# DuplexOptoIso.net
KiCad netlist of a schematic drawn in EAGLE
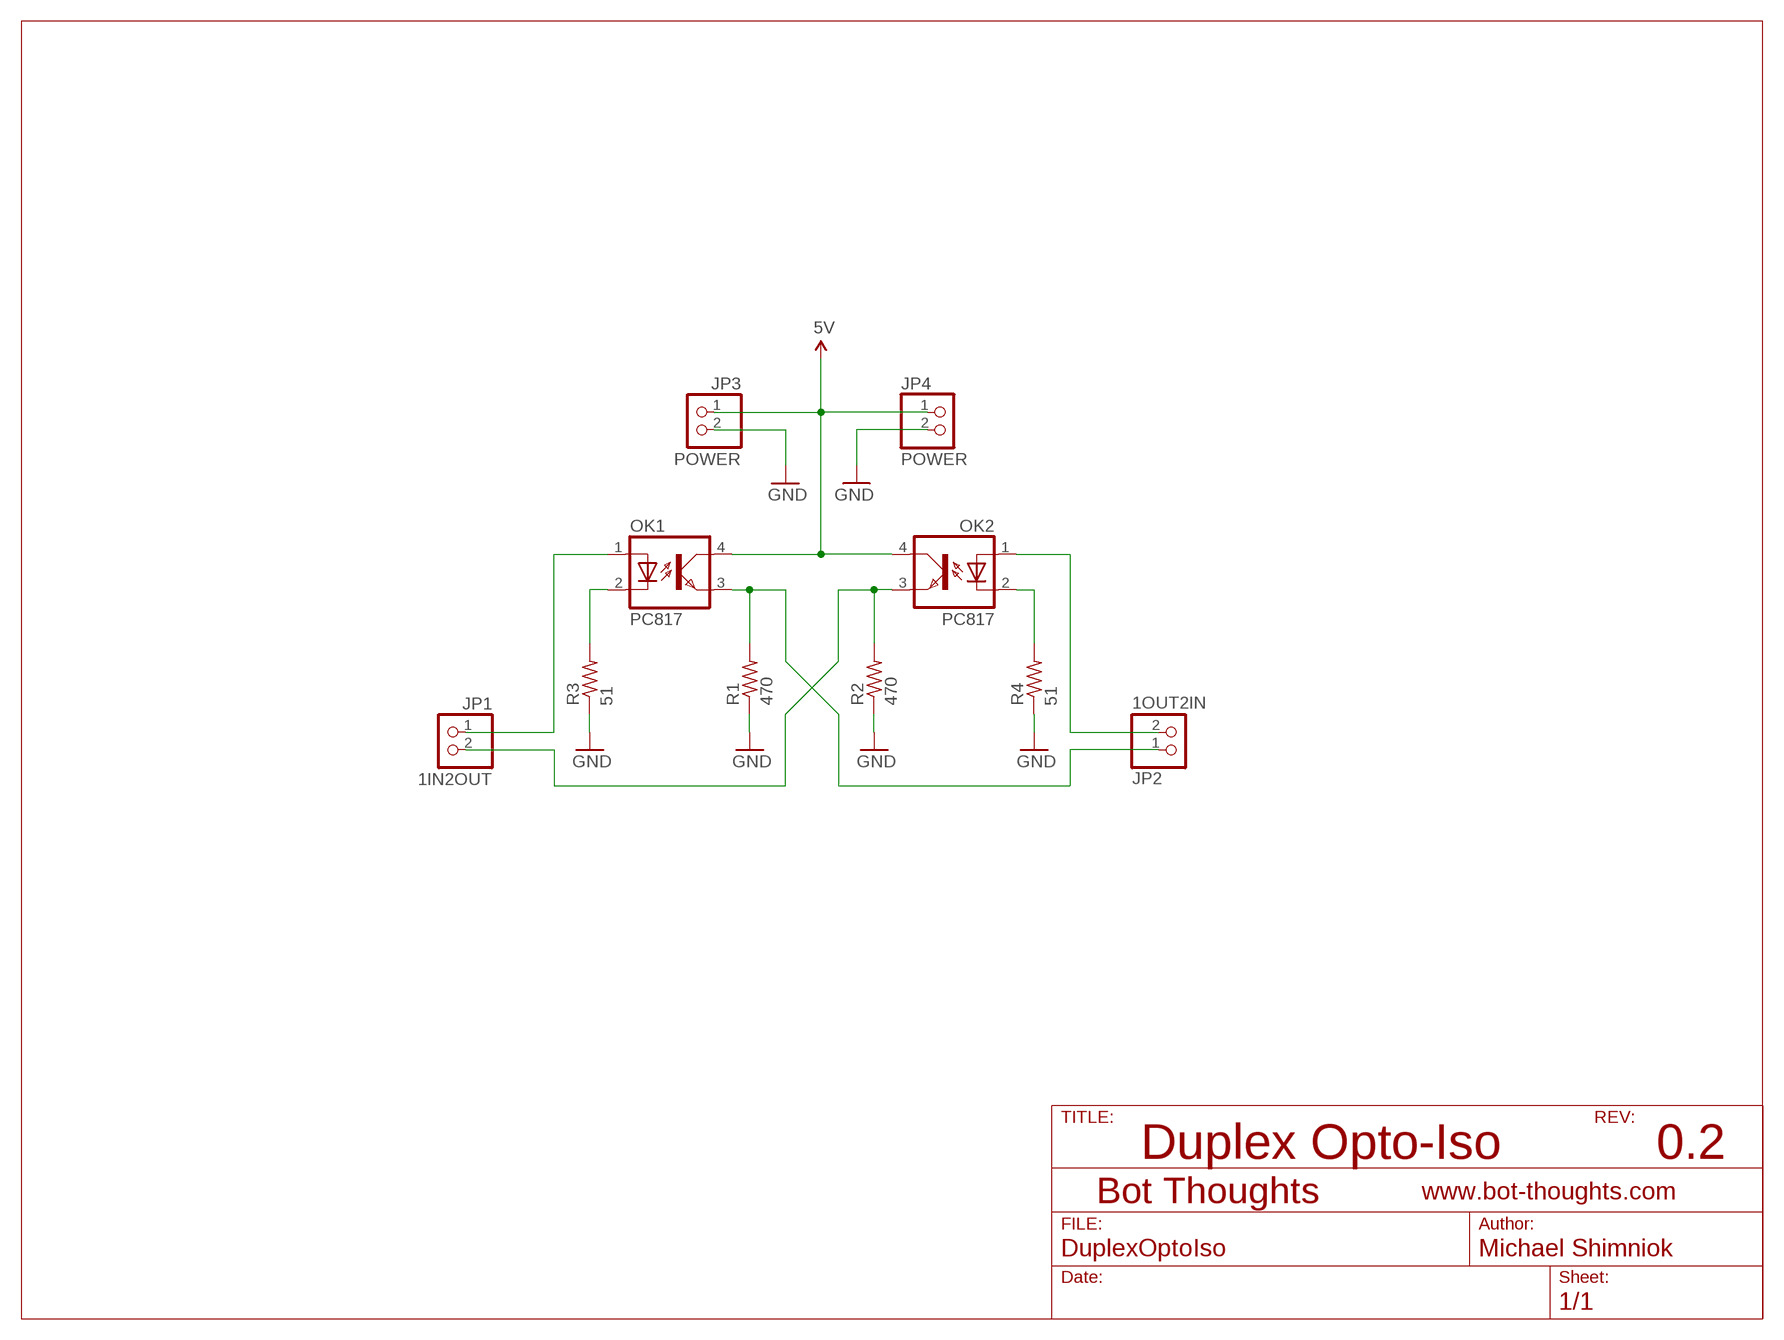
[diagram p0: schematic, sheet 1]

(export (version "E")
  (design (tool "Eeschema 10.0.6"))
  (components
    (comp (ref "JP1")
      (value "1IN2OUT")
      (footprint "eagle-import:1X02-S")
      (libsource (lib "eagle-import") (part "PINHD-1X02_2.54-S"))
    )
    (comp (ref "JP2")
      (value "1OUT2IN")
      (footprint "eagle-import:1X02-S")
      (libsource (lib "eagle-import") (part "PINHD-1X02_2.54-S"))
    )
    (comp (ref "JP3")
      (value "POWER")
      (footprint "eagle-import:1X02-S")
      (libsource (lib "eagle-import") (part "PINHD-1X02_2.54-S"))
    )
    (comp (ref "JP4")
      (value "POWER")
      (footprint "eagle-import:1X02-S")
      (libsource (lib "eagle-import") (part "PINHD-1X02_2.54-S"))
    )
    (comp (ref "OK1")
      (value "PC817")
      (footprint "eagle-import:DIL04")
      (fields (field (name "MPN") "PC817X4J000F"))
      (libsource (lib "eagle-import") (part "PC817"))
    )
    (comp (ref "OK2")
      (value "PC817")
      (footprint "eagle-import:DIL04")
      (fields (field (name "MPN") "PC817X4J000F"))
      (libsource (lib "eagle-import") (part "PC817"))
    )
    (comp (ref "R1")
      (value "470")
      (footprint "eagle-import:0204_5")
      (libsource (lib "eagle-import") (part "R-US_0204/5"))
    )
    (comp (ref "R2")
      (value "470")
      (footprint "eagle-import:0204_5")
      (libsource (lib "eagle-import") (part "R-US_0204/5"))
    )
    (comp (ref "R3")
      (value "51")
      (footprint "eagle-import:0204_5")
      (libsource (lib "eagle-import") (part "R-US_0204/5"))
    )
    (comp (ref "R4")
      (value "51")
      (footprint "eagle-import:0204_5")
      (libsource (lib "eagle-import") (part "R-US_0204/5"))
    )
  )
  (nets
    (net (code "1") (name "5V") (class "Default")
      (node (ref "JP3") (pin "1") (pinfunction "1_1") (pintype "passive"))
      (node (ref "JP4") (pin "1") (pinfunction "1_1") (pintype "passive"))
      (node (ref "OK1") (pin "4") (pinfunction "COL_4") (pintype "passive"))
      (node (ref "OK2") (pin "4") (pinfunction "COL_4") (pintype "passive"))
    )
    (net (code "2") (name "GND") (class "Default")
      (node (ref "JP3") (pin "2") (pinfunction "2_2") (pintype "passive"))
      (node (ref "JP4") (pin "2") (pinfunction "2_2") (pintype "passive"))
      (node (ref "R1") (pin "1") (pinfunction "1_1") (pintype "passive"))
      (node (ref "R2") (pin "1") (pinfunction "1_1") (pintype "passive"))
      (node (ref "R3") (pin "1") (pinfunction "1_1") (pintype "passive"))
      (node (ref "R4") (pin "1") (pinfunction "1_1") (pintype "passive"))
    )
    (net (code "3") (name "Net-(OK1-A)") (class "Default")
      (node (ref "JP1") (pin "1") (pinfunction "1_1") (pintype "passive"))
      (node (ref "OK1") (pin "1") (pinfunction "A_1") (pintype "passive"))
    )
    (net (code "4") (name "Net-(OK1-C)") (class "Default")
      (node (ref "OK1") (pin "2") (pinfunction "C_2") (pintype "passive"))
      (node (ref "R3") (pin "2") (pinfunction "2_2") (pintype "passive"))
    )
    (net (code "5") (name "Net-(OK1-EMIT)") (class "Default")
      (node (ref "JP2") (pin "1") (pinfunction "1_1") (pintype "passive"))
      (node (ref "OK1") (pin "3") (pinfunction "EMIT_3") (pintype "passive"))
      (node (ref "R1") (pin "2") (pinfunction "2_2") (pintype "passive"))
    )
    (net (code "6") (name "Net-(OK2-A)") (class "Default")
      (node (ref "JP2") (pin "2") (pinfunction "2_2") (pintype "passive"))
      (node (ref "OK2") (pin "1") (pinfunction "A_1") (pintype "passive"))
    )
    (net (code "7") (name "Net-(OK2-C)") (class "Default")
      (node (ref "OK2") (pin "2") (pinfunction "C_2") (pintype "passive"))
      (node (ref "R4") (pin "2") (pinfunction "2_2") (pintype "passive"))
    )
    (net (code "8") (name "Net-(OK2-EMIT)") (class "Default")
      (node (ref "JP1") (pin "2") (pinfunction "2_2") (pintype "passive"))
      (node (ref "OK2") (pin "3") (pinfunction "EMIT_3") (pintype "passive"))
      (node (ref "R2") (pin "2") (pinfunction "2_2") (pintype "passive"))
    )
  )
)
